# promini.net
KiCad netlist of a schematic drawn in EAGLE
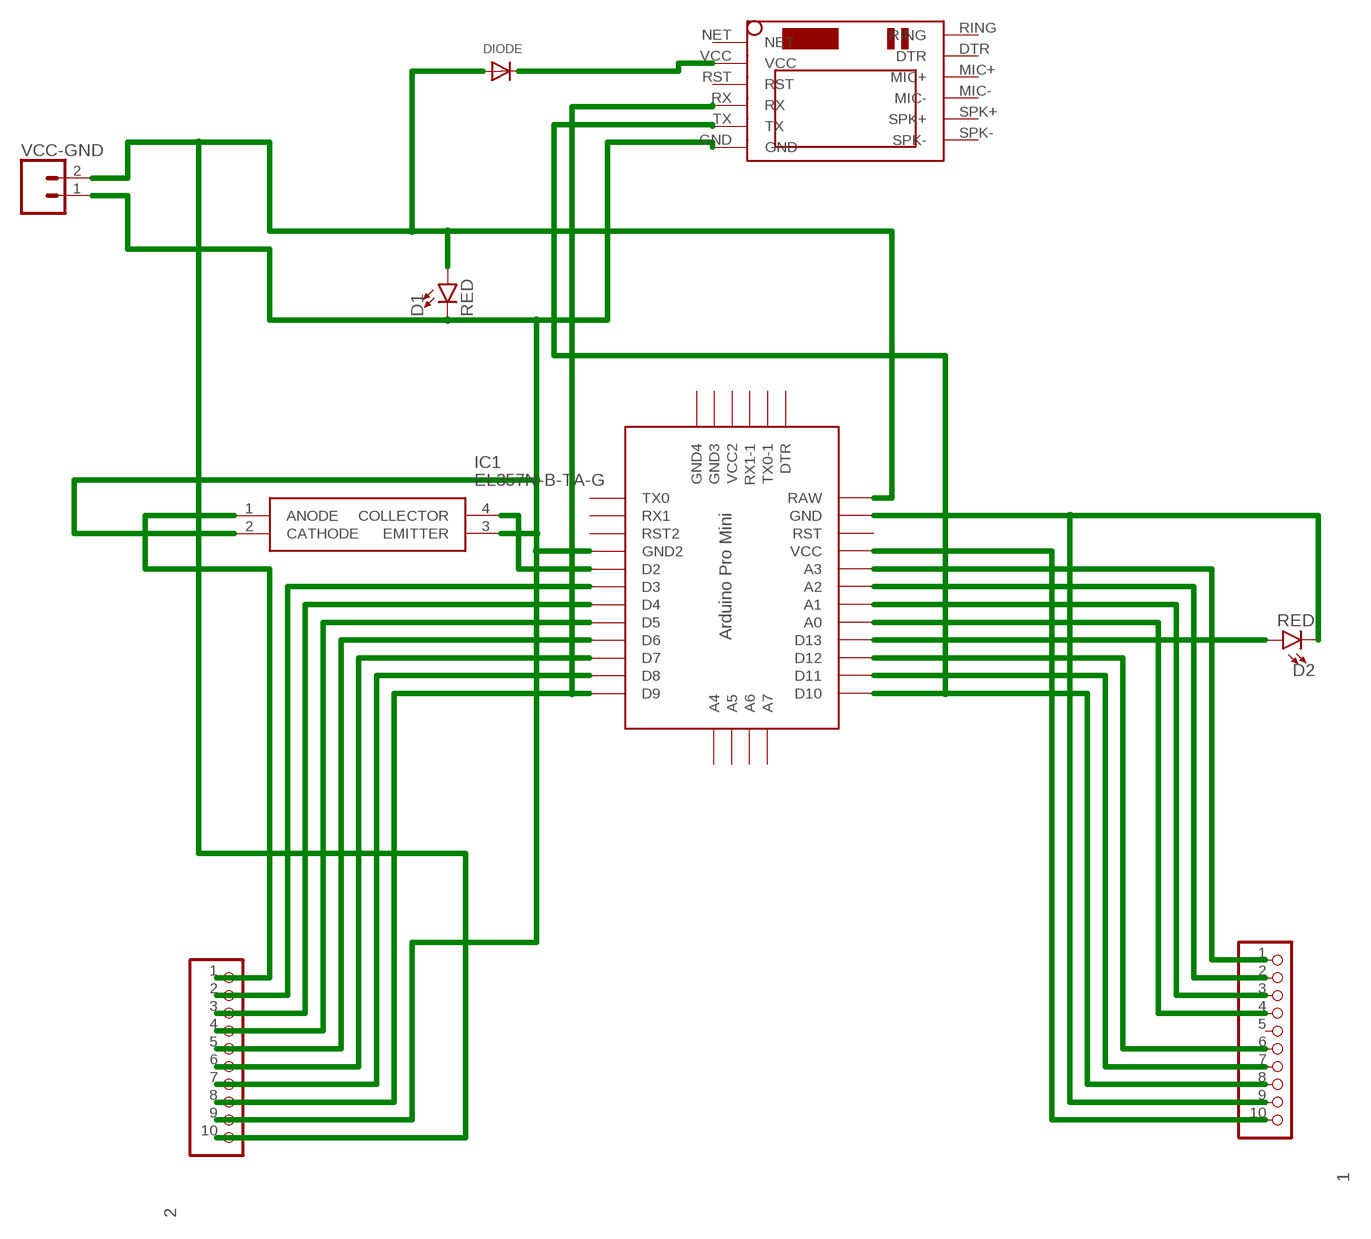
[diagram p0: schematic, sheet 1]

(export (version "E")
  (design (tool "Eeschema 10.0.6"))
  (components
    (comp (ref "1")
      (value "PINHD-1X10")
      (footprint "eagle-import:1X10")
      (libsource (lib "eagle-import") (part "PINHD-1X10"))
    )
    (comp (ref "2")
      (value "PINHD-1X10")
      (footprint "eagle-import:1X10")
      (libsource (lib "eagle-import") (part "PINHD-1X10"))
    )
    (comp (ref "D1")
      (value "RED")
      (footprint "eagle-import:LED-1206")
      (libsource (lib "eagle-import") (part "LED-RED1206"))
    )
    (comp (ref "D2")
      (value "RED")
      (footprint "eagle-import:LED-1206")
      (libsource (lib "eagle-import") (part "LED-RED1206"))
    )
    (comp (ref "DIODE")
      (value "DIODESOD-323F")
      (footprint "eagle-import:SOD-323F")
      (libsource (lib "eagle-import") (part "DIODESOD-323F"))
    )
    (comp (ref "IC1")
      (value "EL357N-B-TA-G")
      (footprint "eagle-import:SOP254P700X200-4N")
      (libsource (lib "eagle-import") (part "EL357N-B-TA-G"))
    )
    (comp (ref "PROMINI")
      (value "PRO-MINI")
      (footprint "eagle-import:PRO-MINI")
      (libsource (lib "eagle-import") (part "PRO-MINI"))
    )
    (comp (ref "U$1")
      (value "SIM800LMODULE")
      (footprint "eagle-import:SIM800LMODULE")
      (libsource (lib "eagle-import") (part "SIM800LMODULE"))
    )
    (comp (ref "VCC-GND")
      (value "CONN_023.5MM")
      (footprint "eagle-import:SCREWTERMINAL-3.5MM-2")
      (libsource (lib "eagle-import") (part "CONN_023.5MM"))
    )
  )
  (nets
    (net (code "1") (name "Net-(1-Pad1)") (class "Default")
      (node (ref "1") (pin "1") (pinfunction "1_1") (pintype "passive"))
      (node (ref "PROMINI") (pin "A3") (pinfunction "A3_A3") (pintype "bidirectional"))
    )
    (net (code "2") (name "Net-(1-Pad2)") (class "Default")
      (node (ref "1") (pin "2") (pinfunction "2_2") (pintype "passive"))
      (node (ref "PROMINI") (pin "A2") (pinfunction "A2_A2") (pintype "bidirectional"))
    )
    (net (code "3") (name "Net-(1-Pad3)") (class "Default")
      (node (ref "1") (pin "3") (pinfunction "3_3") (pintype "passive"))
      (node (ref "PROMINI") (pin "A1") (pinfunction "A1_A1") (pintype "bidirectional"))
    )
    (net (code "4") (name "Net-(1-Pad4)") (class "Default")
      (node (ref "1") (pin "4") (pinfunction "4_4") (pintype "passive"))
      (node (ref "PROMINI") (pin "A0") (pinfunction "A0_A0") (pintype "bidirectional"))
    )
    (net (code "5") (name "Net-(1-Pad6)") (class "Default")
      (node (ref "1") (pin "6") (pinfunction "6_6") (pintype "passive"))
      (node (ref "PROMINI") (pin "D12") (pinfunction "D12_D12") (pintype "bidirectional"))
    )
    (net (code "6") (name "Net-(1-Pad7)") (class "Default")
      (node (ref "1") (pin "7") (pinfunction "7_7") (pintype "passive"))
      (node (ref "PROMINI") (pin "D11") (pinfunction "D11_D11") (pintype "bidirectional"))
    )
    (net (code "7") (name "Net-(1-Pad8)") (class "Default")
      (node (ref "1") (pin "8") (pinfunction "8_8") (pintype "passive"))
      (node (ref "PROMINI") (pin "D10") (pinfunction "D10_D10") (pintype "bidirectional"))
      (node (ref "U$1") (pin "TX") (pinfunction "TX_TX") (pintype "bidirectional"))
    )
    (net (code "8") (name "Net-(1-Pad9)") (class "Default")
      (node (ref "1") (pin "9") (pinfunction "9_9") (pintype "passive"))
      (node (ref "D2") (pin "C") (pinfunction "C_C") (pintype "passive"))
      (node (ref "PROMINI") (pin "GND") (pinfunction "GND_GND") (pintype "input"))
    )
    (net (code "9") (name "Net-(1-Pad10)") (class "Default")
      (node (ref "1") (pin "10") (pinfunction "10_10") (pintype "passive"))
      (node (ref "PROMINI") (pin "VCC") (pinfunction "VCC_VCC") (pintype "bidirectional"))
    )
    (net (code "10") (name "Net-(2-Pad2)") (class "Default")
      (node (ref "2") (pin "2") (pinfunction "2_2") (pintype "passive"))
      (node (ref "PROMINI") (pin "D3") (pinfunction "D3_D3") (pintype "bidirectional"))
    )
    (net (code "11") (name "Net-(2-Pad3)") (class "Default")
      (node (ref "2") (pin "3") (pinfunction "3_3") (pintype "passive"))
      (node (ref "PROMINI") (pin "D4") (pinfunction "D4_D4") (pintype "bidirectional"))
    )
    (net (code "12") (name "Net-(2-Pad4)") (class "Default")
      (node (ref "2") (pin "4") (pinfunction "4_4") (pintype "passive"))
      (node (ref "PROMINI") (pin "D5") (pinfunction "D5_D5") (pintype "bidirectional"))
    )
    (net (code "13") (name "Net-(2-Pad5)") (class "Default")
      (node (ref "2") (pin "5") (pinfunction "5_5") (pintype "passive"))
      (node (ref "PROMINI") (pin "D6") (pinfunction "D6_D6") (pintype "bidirectional"))
    )
    (net (code "14") (name "Net-(2-Pad6)") (class "Default")
      (node (ref "2") (pin "6") (pinfunction "6_6") (pintype "passive"))
      (node (ref "PROMINI") (pin "D7") (pinfunction "D7_D7") (pintype "bidirectional"))
    )
    (net (code "15") (name "Net-(2-Pad7)") (class "Default")
      (node (ref "2") (pin "7") (pinfunction "7_7") (pintype "passive"))
      (node (ref "PROMINI") (pin "D8") (pinfunction "D8_D8") (pintype "bidirectional"))
    )
    (net (code "16") (name "Net-(2-Pad8)") (class "Default")
      (node (ref "2") (pin "8") (pinfunction "8_8") (pintype "passive"))
      (node (ref "PROMINI") (pin "D9") (pinfunction "D9_D9") (pintype "bidirectional"))
      (node (ref "U$1") (pin "RX") (pinfunction "RX_RX") (pintype "bidirectional"))
    )
    (net (code "17") (name "Net-(2-Pad10)") (class "Default")
      (node (ref "2") (pin "10") (pinfunction "10_10") (pintype "passive"))
      (node (ref "D1") (pin "A") (pinfunction "A_A") (pintype "passive"))
      (node (ref "DIODE") (pin "A") (pinfunction "A_A") (pintype "passive"))
      (node (ref "PROMINI") (pin "RAW") (pinfunction "RAW_RAW") (pintype "power_in"))
      (node (ref "VCC-GND") (pin "2") (pinfunction "2_2") (pintype "passive"))
    )
    (net (code "18") (name "Net-(D2-PadA)") (class "Default")
      (node (ref "D2") (pin "A") (pinfunction "A_A") (pintype "passive"))
      (node (ref "PROMINI") (pin "D13") (pinfunction "D13_D13") (pintype "bidirectional"))
    )
    (net (code "19") (name "Net-(DIODE-PadC)") (class "Default")
      (node (ref "DIODE") (pin "C") (pinfunction "C_C") (pintype "passive"))
      (node (ref "U$1") (pin "VCC") (pinfunction "VCC_VCC") (pintype "bidirectional"))
    )
    (net (code "20") (name "Net-(IC1-ANODE)") (class "Default")
      (node (ref "2") (pin "1") (pinfunction "1_1") (pintype "passive"))
      (node (ref "IC1") (pin "1") (pinfunction "ANODE_1") (pintype "bidirectional"))
    )
    (net (code "21") (name "Net-(IC1-CATHODE)") (class "Default")
      (node (ref "2") (pin "9") (pinfunction "9_9") (pintype "passive"))
      (node (ref "D1") (pin "C") (pinfunction "C_C") (pintype "passive"))
      (node (ref "IC1") (pin "2") (pinfunction "CATHODE_2") (pintype "bidirectional"))
      (node (ref "IC1") (pin "3") (pinfunction "EMITTER_3") (pintype "bidirectional"))
      (node (ref "PROMINI") (pin "GND1") (pinfunction "GND2_GND1") (pintype "bidirectional"))
      (node (ref "U$1") (pin "GND") (pinfunction "GND_GND") (pintype "bidirectional"))
      (node (ref "VCC-GND") (pin "1") (pinfunction "1_1") (pintype "passive"))
    )
    (net (code "22") (name "Net-(IC1-COLLECTOR)") (class "Default")
      (node (ref "IC1") (pin "4") (pinfunction "COLLECTOR_4") (pintype "bidirectional"))
      (node (ref "PROMINI") (pin "D2") (pinfunction "D2_D2") (pintype "bidirectional"))
    )
    (net (code "23") (name "unconnected-(1-Pad5)") (class "Default")
      (node (ref "1") (pin "5") (pinfunction "5_5") (pintype "passive"))
    )
    (net (code "24") (name "unconnected-(PROMINI-GND4-PadGND2)") (class "Default")
      (node (ref "PROMINI") (pin "GND2") (pinfunction "GND4_GND2") (pintype "bidirectional"))
    )
    (net (code "25") (name "unconnected-(PROMINI-PadA4)") (class "Default")
      (node (ref "PROMINI") (pin "A4") (pinfunction "A4_A4") (pintype "bidirectional"))
    )
    (net (code "26") (name "unconnected-(PROMINI-PadA5)") (class "Default")
      (node (ref "PROMINI") (pin "A5") (pinfunction "A5_A5") (pintype "bidirectional"))
    )
    (net (code "27") (name "unconnected-(PROMINI-PadA6)") (class "Default")
      (node (ref "PROMINI") (pin "A6") (pinfunction "A6_A6") (pintype "bidirectional"))
    )
    (net (code "28") (name "unconnected-(PROMINI-PadA7)") (class "Default")
      (node (ref "PROMINI") (pin "A7") (pinfunction "A7_A7") (pintype "bidirectional"))
    )
    (net (code "29") (name "unconnected-(PROMINI-PadDTR)") (class "Default")
      (node (ref "PROMINI") (pin "DTR") (pinfunction "DTR_DTR") (pintype "bidirectional"))
    )
    (net (code "30") (name "unconnected-(PROMINI-PadGND3)") (class "Default")
      (node (ref "PROMINI") (pin "GND3") (pinfunction "GND3_GND3") (pintype "bidirectional"))
    )
    (net (code "31") (name "unconnected-(PROMINI-PadRST)") (class "Default")
      (node (ref "PROMINI") (pin "RST") (pinfunction "RST_RST") (pintype "bidirectional"))
    )
    (net (code "32") (name "unconnected-(PROMINI-PadRX1)") (class "Default")
      (node (ref "PROMINI") (pin "RX1") (pinfunction "RX1_RX1") (pintype "bidirectional"))
    )
    (net (code "33") (name "unconnected-(PROMINI-PadRX1-1)") (class "Default")
      (node (ref "PROMINI") (pin "RX1-1") (pinfunction "RX1-1_RX1-1") (pintype "bidirectional"))
    )
    (net (code "34") (name "unconnected-(PROMINI-PadTX0)") (class "Default")
      (node (ref "PROMINI") (pin "TX0") (pinfunction "TX0_TX0") (pintype "bidirectional"))
    )
    (net (code "35") (name "unconnected-(PROMINI-PadTX0-1)") (class "Default")
      (node (ref "PROMINI") (pin "TX0-1") (pinfunction "TX0-1_TX0-1") (pintype "bidirectional"))
    )
    (net (code "36") (name "unconnected-(PROMINI-RST2-PadRST1)") (class "Default")
      (node (ref "PROMINI") (pin "RST1") (pinfunction "RST2_RST1") (pintype "bidirectional"))
    )
    (net (code "37") (name "unconnected-(PROMINI-VCC2-PadVCC1)") (class "Default")
      (node (ref "PROMINI") (pin "VCC1") (pinfunction "VCC2_VCC1") (pintype "bidirectional"))
    )
    (net (code "38") (name "unconnected-(U$1-PadDTR)") (class "Default")
      (node (ref "U$1") (pin "DTR") (pinfunction "DTR_DTR") (pintype "bidirectional"))
    )
    (net (code "39") (name "unconnected-(U$1-PadMIC+)") (class "Default")
      (node (ref "U$1") (pin "MIC+") (pinfunction "MIC+_MIC+") (pintype "bidirectional"))
    )
    (net (code "40") (name "unconnected-(U$1-PadMIC-)") (class "Default")
      (node (ref "U$1") (pin "MIC-") (pinfunction "MIC-_MIC-") (pintype "bidirectional"))
    )
    (net (code "41") (name "unconnected-(U$1-PadNET)") (class "Default")
      (node (ref "U$1") (pin "NET") (pinfunction "NET_NET") (pintype "bidirectional"))
    )
    (net (code "42") (name "unconnected-(U$1-PadRING)") (class "Default")
      (node (ref "U$1") (pin "RING") (pinfunction "RING_RING") (pintype "bidirectional"))
    )
    (net (code "43") (name "unconnected-(U$1-PadRST)") (class "Default")
      (node (ref "U$1") (pin "RST") (pinfunction "RST_RST") (pintype "bidirectional"))
    )
    (net (code "44") (name "unconnected-(U$1-PadSPK+)") (class "Default")
      (node (ref "U$1") (pin "SPK+") (pinfunction "SPK+_SPK+") (pintype "bidirectional"))
    )
    (net (code "45") (name "unconnected-(U$1-PadSPK-)") (class "Default")
      (node (ref "U$1") (pin "SPK-") (pinfunction "SPK-_SPK-") (pintype "bidirectional"))
    )
  )
)
